# TF_CARD.net
KiCad netlist of a schematic drawn in Altium Designer
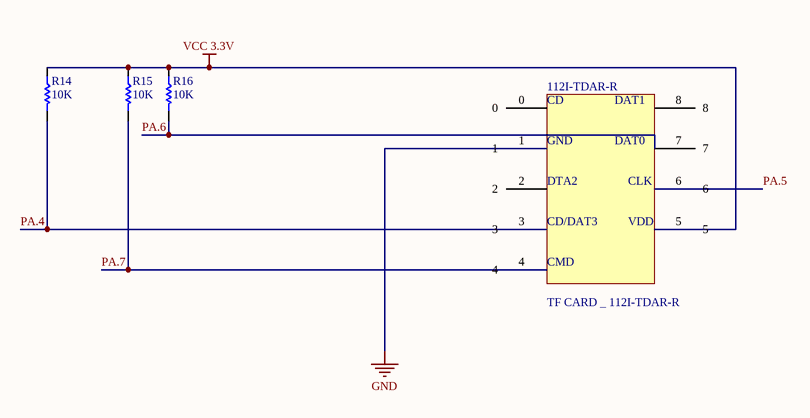
[diagram p0: TF CARD.SchDoc]

(export (version "E")
  (design (tool "Eeschema 10.0.6"))
  (components
    (comp (ref "112I-TDAR-R")
      (value "ATTEND")
      (footprint "PCBComponent_1")
      (libsource (lib "TD CARD _112I-TDAR-R.Schlib1") (part "Component_1"))
    )
    (comp (ref "R14")
      (value "10K")
      (footprint "SMD_RES_0805")
      (description "Resistor")
      (fields (field (name "TOLERANCE") "5%") (field (name "POWER") "1/8 W"))
      (libsource (lib "DDEmS Library") (part "Resistor"))
    )
    (comp (ref "R15")
      (value "10K")
      (footprint "SMD_RES_0805")
      (description "Resistor")
      (fields (field (name "TOLERANCE") "5%") (field (name "POWER") "1/8 W"))
      (libsource (lib "DDEmS Library") (part "Resistor"))
    )
    (comp (ref "R16")
      (value "10K")
      (footprint "SMD_RES_0805")
      (description "Resistor")
      (fields (field (name "TOLERANCE") "5%") (field (name "POWER") "1/8 W"))
      (libsource (lib "DDEmS Library") (part "Resistor"))
    )
  )
  (nets
    (net (code "1") (name "/PA.4") (class "Default")
      (node (ref "112I-TDAR-R") (pin "3") (pinfunction "3_3") (pintype "passive"))
      (node (ref "R14") (pin "2") (pinfunction "2_2") (pintype "passive"))
    )
    (net (code "2") (name "/PA.5") (class "Default")
      (node (ref "112I-TDAR-R") (pin "6") (pinfunction "6_6") (pintype "passive"))
    )
    (net (code "3") (name "/PA.6") (class "Default")
      (node (ref "112I-TDAR-R") (pin "7") (pinfunction "7_7") (pintype "passive"))
      (node (ref "R16") (pin "2") (pinfunction "2_2") (pintype "passive"))
    )
    (net (code "4") (name "/PA.7") (class "Default")
      (node (ref "112I-TDAR-R") (pin "4") (pinfunction "4_4") (pintype "passive"))
      (node (ref "R15") (pin "2") (pinfunction "2_2") (pintype "passive"))
    )
    (net (code "5") (name "GND") (class "Default")
      (node (ref "112I-TDAR-R") (pin "1") (pinfunction "1_1") (pintype "passive"))
    )
    (net (code "6") (name "VCC 3.3V") (class "Default")
      (node (ref "112I-TDAR-R") (pin "5") (pinfunction "5_5") (pintype "passive"))
      (node (ref "R14") (pin "1") (pinfunction "1_1") (pintype "passive"))
      (node (ref "R15") (pin "1") (pinfunction "1_1") (pintype "passive"))
      (node (ref "R16") (pin "1") (pinfunction "1_1") (pintype "passive"))
    )
    (net (code "7") (name "unconnected-(112I-TDAR-R-Pad0)") (class "Default")
      (node (ref "112I-TDAR-R") (pin "0") (pinfunction "0_0") (pintype "passive"))
    )
    (net (code "8") (name "unconnected-(112I-TDAR-R-Pad2)") (class "Default")
      (node (ref "112I-TDAR-R") (pin "2") (pinfunction "2_2") (pintype "passive"))
    )
    (net (code "9") (name "unconnected-(112I-TDAR-R-Pad8)") (class "Default")
      (node (ref "112I-TDAR-R") (pin "8") (pinfunction "8_8") (pintype "passive"))
    )
  )
)
